# POWER.net
KiCad netlist of a schematic drawn in Altium Designer
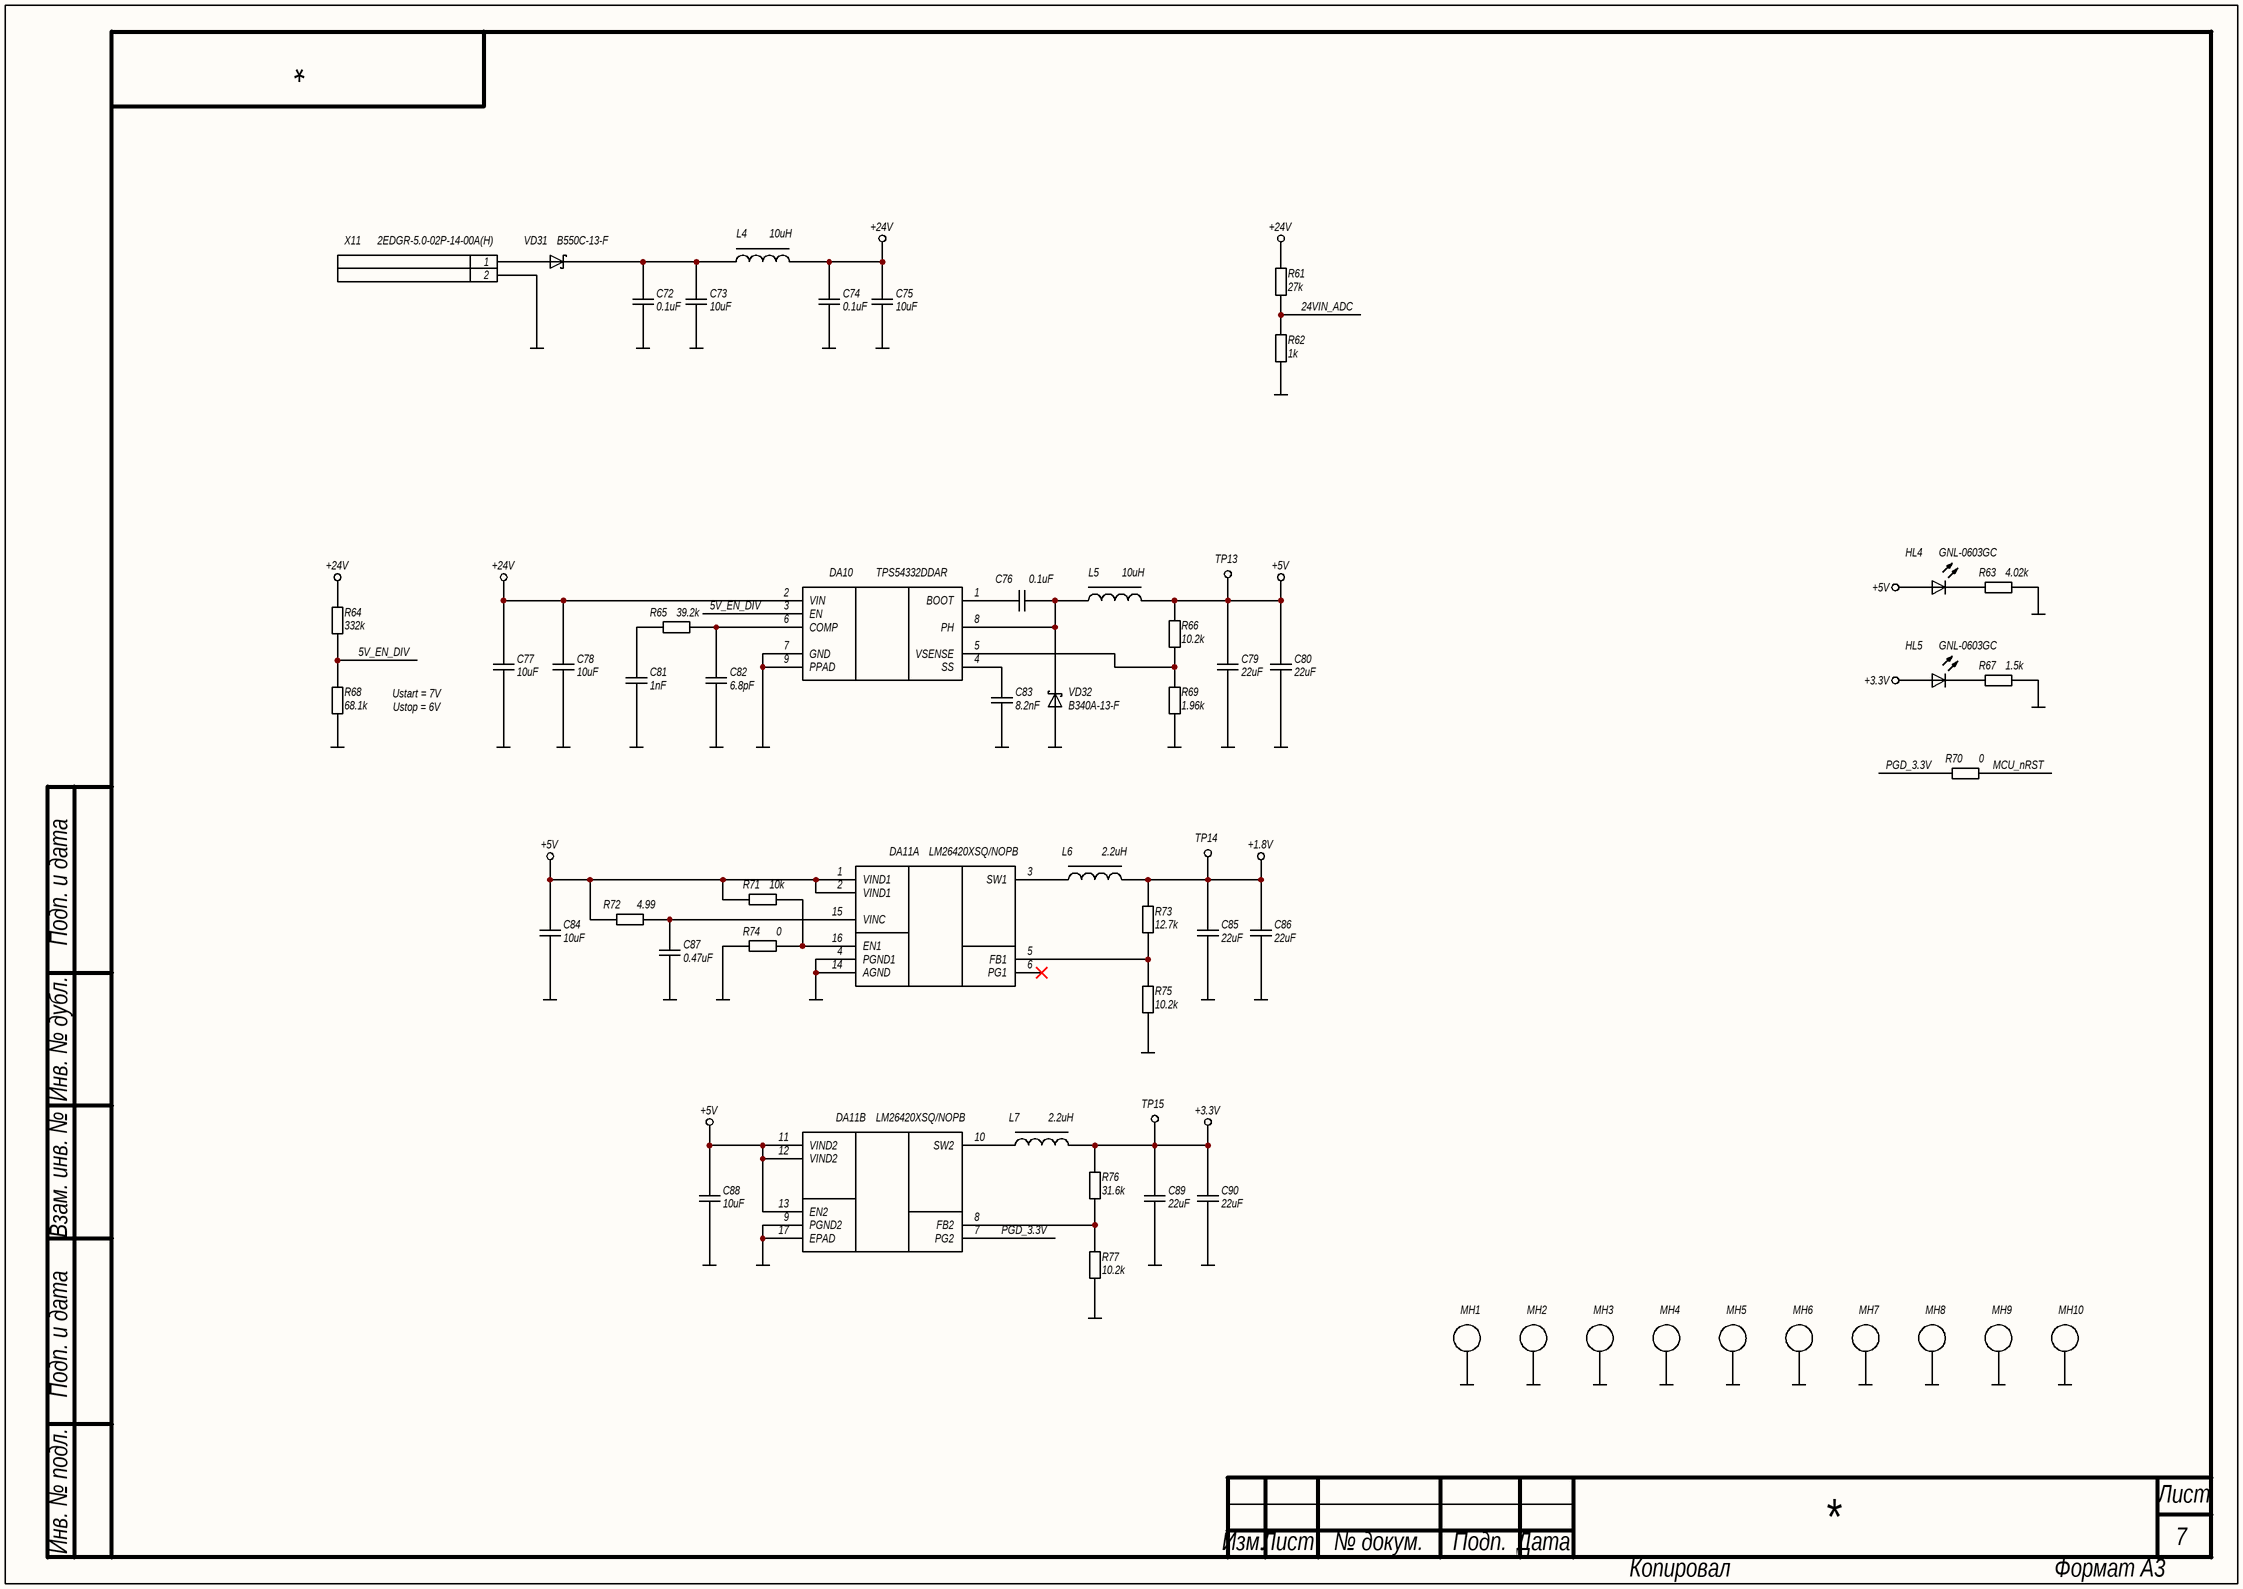
[diagram p0: POWER.SchDoc]

(export (version "E")
  (design (tool "Eeschema 10.0.6"))
  (components
    (comp (ref "C72")
      (value "0.1uF")
      (footprint "C0805N")
      (description "Конденсатор")
      (libsource (lib "Components Library") (part "CAP_FIXED"))
    )
    (comp (ref "C73")
      (value "10uF")
      (footprint "C1206N")
      (description "Конденсатор")
      (libsource (lib "Components Library") (part "CAP_FIXED"))
    )
    (comp (ref "C74")
      (value "0.1uF")
      (footprint "C0805N")
      (description "Конденсатор")
      (libsource (lib "Components Library") (part "CAP_FIXED"))
    )
    (comp (ref "C75")
      (value "10uF")
      (footprint "C1206N")
      (description "Конденсатор")
      (libsource (lib "Components Library") (part "CAP_FIXED"))
    )
    (comp (ref "C76")
      (value "0.1uF")
      (footprint "C0603N")
      (description "Конденсатор")
      (libsource (lib "Components Library") (part "CAP_FIXED"))
    )
    (comp (ref "C77")
      (value "10uF")
      (footprint "C1206N")
      (description "Конденсатор")
      (libsource (lib "Components Library") (part "CAP_FIXED"))
    )
    (comp (ref "C78")
      (value "10uF")
      (footprint "C1206N")
      (description "Конденсатор")
      (libsource (lib "Components Library") (part "CAP_FIXED"))
    )
    (comp (ref "C79")
      (value "22uF")
      (footprint "C0805N")
      (description "Конденсатор")
      (libsource (lib "Components Library") (part "CAP_FIXED"))
    )
    (comp (ref "C80")
      (value "22uF")
      (footprint "C0805N")
      (description "Конденсатор")
      (libsource (lib "Components Library") (part "CAP_FIXED"))
    )
    (comp (ref "C81")
      (value "1nF")
      (footprint "C0603N")
      (description "Конденсатор")
      (libsource (lib "Components Library") (part "CAP_FIXED"))
    )
    (comp (ref "C82")
      (value "6.8pF")
      (footprint "C0603N")
      (description "Конденсатор")
      (libsource (lib "Components Library") (part "CAP_FIXED"))
    )
    (comp (ref "C83")
      (value "8.2nF")
      (footprint "C0603N")
      (description "Конденсатор")
      (libsource (lib "Components Library") (part "CAP_FIXED"))
    )
    (comp (ref "C84")
      (value "10uF")
      (footprint "C0805N")
      (description "Конденсатор")
      (libsource (lib "Components Library") (part "CAP_FIXED"))
    )
    (comp (ref "C85")
      (value "22uF")
      (footprint "C0805N")
      (description "Конденсатор")
      (libsource (lib "Components Library") (part "CAP_FIXED"))
    )
    (comp (ref "C86")
      (value "22uF")
      (footprint "C0805N")
      (description "Конденсатор")
      (libsource (lib "Components Library") (part "CAP_FIXED"))
    )
    (comp (ref "C87")
      (value "0.47uF")
      (footprint "C0603N")
      (description "Конденсатор")
      (libsource (lib "Components Library") (part "CAP_FIXED"))
    )
    (comp (ref "C88")
      (value "10uF")
      (footprint "C0805N")
      (description "Конденсатор")
      (libsource (lib "Components Library") (part "CAP_FIXED"))
    )
    (comp (ref "C89")
      (value "22uF")
      (footprint "C0805N")
      (description "Конденсатор")
      (libsource (lib "Components Library") (part "CAP_FIXED"))
    )
    (comp (ref "C90")
      (value "22uF")
      (footprint "C0805N")
      (description "Конденсатор")
      (libsource (lib "Components Library") (part "CAP_FIXED"))
    )
    (comp (ref "DA10")
      (value "TPS54332DDAR")
      (footprint "SOIC8-EP")
      (description "Микросхема понижающего преобразователя")
      (libsource (lib "Components Library") (part "TPS54332"))
    )
    (comp (ref "DA11")
      (value "LM26420XSQ/NOPB")
      (footprint "RUM0016A")
      (libsource (lib "Components Library") (part "LM26420X"))
    )
    (comp (ref "HL4")
      (value "GNL-0603GC")
      (footprint "LED0603")
      (description "Светодиод")
      (libsource (lib "Components Library") (part "LED"))
    )
    (comp (ref "HL5")
      (value "GNL-0603GC")
      (footprint "LED0603")
      (description "Светодиод")
      (libsource (lib "Components Library") (part "LED"))
    )
    (comp (ref "L4")
      (value "10uH")
      (footprint "SRN8040")
      (description "Дроссель с магнитопроводом")
      (libsource (lib "Components Library") (part "IND_CORE"))
    )
    (comp (ref "L5")
      (value "10uH")
      (footprint "SRN8040")
      (description "Дроссель с магнитопроводом")
      (libsource (lib "Components Library") (part "IND_CORE"))
    )
    (comp (ref "L6")
      (value "2.2uH")
      (footprint "VLS3012HBX")
      (description "Дроссель с магнитопроводом")
      (libsource (lib "Components Library") (part "IND_CORE"))
    )
    (comp (ref "L7")
      (value "2.2uH")
      (footprint "VLS3012HBX")
      (description "Дроссель с магнитопроводом")
      (libsource (lib "Components Library") (part "IND_CORE"))
    )
    (comp (ref "MH1")
      (value "MNT_HOLE_PL")
      (footprint "MH_3.2_5.4_PLATED_VIA")
      (description "Монтажное отверстие, металлизированное")
      (libsource (lib "Components Library") (part "MNT_HOLE_PL"))
    )
    (comp (ref "MH2")
      (value "MNT_HOLE_PL")
      (footprint "MH_3.2_5.4_PLATED_VIA")
      (description "Монтажное отверстие, металлизированное")
      (libsource (lib "Components Library") (part "MNT_HOLE_PL"))
    )
    (comp (ref "MH3")
      (value "MNT_HOLE_PL")
      (footprint "MH_3.2_5.4_PLATED_VIA")
      (description "Монтажное отверстие, металлизированное")
      (libsource (lib "Components Library") (part "MNT_HOLE_PL"))
    )
    (comp (ref "MH4")
      (value "MNT_HOLE_PL")
      (footprint "MH_3.2_5.4_PLATED_VIA")
      (description "Монтажное отверстие, металлизированное")
      (libsource (lib "Components Library") (part "MNT_HOLE_PL"))
    )
    (comp (ref "MH5")
      (value "MNT_HOLE_PL")
      (footprint "MH_3.2_5.4_PLATED_VIA")
      (description "Монтажное отверстие, металлизированное")
      (libsource (lib "Components Library") (part "MNT_HOLE_PL"))
    )
    (comp (ref "MH6")
      (value "MNT_HOLE_PL")
      (footprint "MH_3.2_5.4_PLATED_VIA")
      (description "Монтажное отверстие, металлизированное")
      (libsource (lib "Components Library") (part "MNT_HOLE_PL"))
    )
    (comp (ref "MH7")
      (value "MNT_HOLE_PL")
      (footprint "MH_3.2_5.4_PLATED_VIA")
      (description "Монтажное отверстие, металлизированное")
      (libsource (lib "Components Library") (part "MNT_HOLE_PL"))
    )
    (comp (ref "MH8")
      (value "MNT_HOLE_PL")
      (footprint "MH_3.2_5.4_PLATED_VIA")
      (description "Монтажное отверстие, металлизированное")
      (libsource (lib "Components Library") (part "MNT_HOLE_PL"))
    )
    (comp (ref "MH9")
      (value "MNT_HOLE_PL")
      (footprint "MH_3.2_5.4_PLATED_VIA")
      (description "Монтажное отверстие, металлизированное")
      (libsource (lib "Components Library") (part "MNT_HOLE_PL"))
    )
    (comp (ref "MH10")
      (value "MNT_HOLE_PL")
      (footprint "MH_3.2_5.4_PLATED_VIA")
      (description "Монтажное отверстие, металлизированное")
      (libsource (lib "Components Library") (part "MNT_HOLE_PL"))
    )
    (comp (ref "R61")
      (value "27k")
      (footprint "R0603N")
      (description "Резистор")
      (libsource (lib "") (part "RES_FIXED_1"))
    )
    (comp (ref "R62")
      (value "1k")
      (footprint "R0603N")
      (description "Резистор")
      (libsource (lib "") (part "RES_FIXED_1"))
    )
    (comp (ref "R63")
      (value "4.02k")
      (footprint "R0603N")
      (description "Резистор")
      (libsource (lib "") (part "RES_FIXED_2"))
    )
    (comp (ref "R64")
      (value "332k")
      (footprint "R0603N")
      (description "Резистор")
      (libsource (lib "Components Library") (part "RES_FIXED"))
    )
    (comp (ref "R65")
      (value "39.2k")
      (footprint "R0603N")
      (description "Резистор")
      (libsource (lib "") (part "RES_FIXED_2"))
    )
    (comp (ref "R66")
      (value "10.2k")
      (footprint "R0603N")
      (description "Резистор")
      (libsource (lib "Components Library") (part "RES_FIXED"))
    )
    (comp (ref "R67")
      (value "1.5k")
      (footprint "R0603N")
      (description "Резистор")
      (libsource (lib "") (part "RES_FIXED_2"))
    )
    (comp (ref "R68")
      (value "68.1k")
      (footprint "R0603N")
      (description "Резистор")
      (libsource (lib "Components Library") (part "RES_FIXED"))
    )
    (comp (ref "R69")
      (value "1.96k")
      (footprint "R0603N")
      (description "Резистор")
      (libsource (lib "Components Library") (part "RES_FIXED"))
    )
    (comp (ref "R70")
      (value "0")
      (footprint "R0603N")
      (description "Резистор")
      (libsource (lib "") (part "RES_FIXED_3"))
    )
    (comp (ref "R71")
      (value "10k")
      (footprint "R0603N")
      (description "Резистор")
      (libsource (lib "") (part "RES_FIXED_2"))
    )
    (comp (ref "R72")
      (value "4.99")
      (footprint "R0603N")
      (description "Резистор")
      (libsource (lib "") (part "RES_FIXED_2"))
    )
    (comp (ref "R73")
      (value "12.7k")
      (footprint "R0603N")
      (description "Резистор")
      (libsource (lib "Components Library") (part "RES_FIXED"))
    )
    (comp (ref "R74")
      (value "0")
      (footprint "R0603N")
      (description "Резистор")
      (libsource (lib "") (part "RES_FIXED_2"))
    )
    (comp (ref "R75")
      (value "10.2k")
      (footprint "R0603N")
      (description "Резистор")
      (libsource (lib "Components Library") (part "RES_FIXED"))
    )
    (comp (ref "R76")
      (value "31.6k")
      (footprint "R0603N")
      (description "Резистор")
      (libsource (lib "Components Library") (part "RES_FIXED"))
    )
    (comp (ref "R77")
      (value "10.2k")
      (footprint "R0603N")
      (description "Резистор")
      (libsource (lib "Components Library") (part "RES_FIXED"))
    )
    (comp (ref "TP13")
      (value "TEST_POINT")
      (footprint "TP_RPAD_0.8MM")
      (description "Контрольная точка")
      (libsource (lib "Components Library") (part "TEST_POINT"))
    )
    (comp (ref "TP14")
      (value "TEST_POINT")
      (footprint "TP_RPAD_0.8MM")
      (description "Контрольная точка")
      (libsource (lib "Components Library") (part "TEST_POINT"))
    )
    (comp (ref "TP15")
      (value "TEST_POINT")
      (footprint "TP_RPAD_0.8MM")
      (description "Контрольная точка")
      (libsource (lib "Components Library") (part "TEST_POINT"))
    )
    (comp (ref "VD31")
      (value "B550C-13-F")
      (footprint "SMC")
      (description "Диод Шоттки")
      (libsource (lib "Components Library") (part "SCHOTTKY"))
    )
    (comp (ref "VD32")
      (value "B340A-13-F")
      (footprint "SMA")
      (description "Диод Шоттки")
      (libsource (lib "Components Library") (part "SCHOTTKY"))
    )
    (comp (ref "X11")
      (value "2EDGR-5.0-02P-14-00A(H)")
      (footprint "2EDGR-5.0-02P-14-00A(H)")
      (description "Разъем, 2 контакта")
      (libsource (lib "Components Library") (part "Connector 2"))
    )
  )
  (nets
    (net (code "1") (name "+1.8V") (class "Default")
      (node (ref "C85") (pin "2") (pinfunction "2_2") (pintype "passive"))
      (node (ref "C86") (pin "2") (pinfunction "2_2") (pintype "passive"))
      (node (ref "L6") (pin "2") (pinfunction "2_2") (pintype "passive"))
      (node (ref "R73") (pin "1") (pinfunction "1_1") (pintype "passive"))
      (node (ref "TP14") (pin "1") (pinfunction "1_1") (pintype "passive"))
    )
    (net (code "2") (name "+3.3V") (class "Default")
      (node (ref "C89") (pin "2") (pinfunction "2_2") (pintype "passive"))
      (node (ref "C90") (pin "2") (pinfunction "2_2") (pintype "passive"))
      (node (ref "HL5") (pin "2") (pinfunction "A_2") (pintype "passive"))
      (node (ref "L7") (pin "2") (pinfunction "2_2") (pintype "passive"))
      (node (ref "R76") (pin "1") (pinfunction "1_1") (pintype "passive"))
      (node (ref "TP15") (pin "1") (pinfunction "1_1") (pintype "passive"))
    )
    (net (code "3") (name "+5V") (class "Default")
      (node (ref "C79") (pin "2") (pinfunction "2_2") (pintype "passive"))
      (node (ref "C80") (pin "2") (pinfunction "2_2") (pintype "passive"))
      (node (ref "C84") (pin "2") (pinfunction "2_2") (pintype "passive"))
      (node (ref "C88") (pin "2") (pinfunction "2_2") (pintype "passive"))
      (node (ref "DA11") (pin "1") (pinfunction "VIND1_1") (pintype "power_in"))
      (node (ref "DA11") (pin "11") (pinfunction "VIND2_11") (pintype "power_in"))
      (node (ref "DA11") (pin "12") (pinfunction "VIND2_12") (pintype "power_in"))
      (node (ref "DA11") (pin "13") (pinfunction "EN2_13") (pintype "power_in"))
      (node (ref "DA11") (pin "2") (pinfunction "VIND1_2") (pintype "power_in"))
      (node (ref "HL4") (pin "2") (pinfunction "A_2") (pintype "passive"))
      (node (ref "L5") (pin "2") (pinfunction "2_2") (pintype "passive"))
      (node (ref "R66") (pin "1") (pinfunction "1_1") (pintype "passive"))
      (node (ref "R71") (pin "2") (pinfunction "2_2") (pintype "passive"))
      (node (ref "R72") (pin "2") (pinfunction "2_2") (pintype "passive"))
      (node (ref "TP13") (pin "1") (pinfunction "1_1") (pintype "passive"))
    )
    (net (code "4") (name "+24V") (class "Default")
      (node (ref "C74") (pin "2") (pinfunction "2_2") (pintype "passive"))
      (node (ref "C75") (pin "2") (pinfunction "2_2") (pintype "passive"))
      (node (ref "C77") (pin "2") (pinfunction "2_2") (pintype "passive"))
      (node (ref "C78") (pin "2") (pinfunction "2_2") (pintype "passive"))
      (node (ref "DA10") (pin "2") (pinfunction "VIN_2") (pintype "power_in"))
      (node (ref "L4") (pin "2") (pinfunction "2_2") (pintype "passive"))
      (node (ref "R61") (pin "2") (pinfunction "2_2") (pintype "passive"))
      (node (ref "R64") (pin "1") (pinfunction "1_1") (pintype "passive"))
    )
    (net (code "5") (name "/5V_EN_DIV") (class "Default")
      (node (ref "DA10") (pin "3") (pinfunction "EN_3") (pintype "power_in"))
      (node (ref "R64") (pin "2") (pinfunction "2_2") (pintype "passive"))
      (node (ref "R68") (pin "1") (pinfunction "1_1") (pintype "passive"))
    )
    (net (code "6") (name "/24VIN_ADC") (class "Default")
      (node (ref "R61") (pin "1") (pinfunction "1_1") (pintype "passive"))
      (node (ref "R62") (pin "2") (pinfunction "2_2") (pintype "passive"))
    )
    (net (code "7") (name "/MCU_nRST") (class "Default")
      (node (ref "R70") (pin "2") (pinfunction "2_2") (pintype "passive"))
    )
    (net (code "8") (name "/PGD_3.3V") (class "Default")
      (node (ref "DA11") (pin "7") (pinfunction "PG2_7") (pintype "power_in"))
      (node (ref "R70") (pin "1") (pinfunction "1_1") (pintype "passive"))
    )
    (net (code "9") (name "GND") (class "Default")
      (node (ref "C72") (pin "1") (pinfunction "1_1") (pintype "passive"))
      (node (ref "C73") (pin "1") (pinfunction "1_1") (pintype "passive"))
      (node (ref "C74") (pin "1") (pinfunction "1_1") (pintype "passive"))
      (node (ref "C75") (pin "1") (pinfunction "1_1") (pintype "passive"))
      (node (ref "C77") (pin "1") (pinfunction "1_1") (pintype "passive"))
      (node (ref "C78") (pin "1") (pinfunction "1_1") (pintype "passive"))
      (node (ref "C79") (pin "1") (pinfunction "1_1") (pintype "passive"))
      (node (ref "C80") (pin "1") (pinfunction "1_1") (pintype "passive"))
      (node (ref "C81") (pin "1") (pinfunction "1_1") (pintype "passive"))
      (node (ref "C82") (pin "1") (pinfunction "1_1") (pintype "passive"))
      (node (ref "C83") (pin "1") (pinfunction "1_1") (pintype "passive"))
      (node (ref "C84") (pin "1") (pinfunction "1_1") (pintype "passive"))
      (node (ref "C85") (pin "1") (pinfunction "1_1") (pintype "passive"))
      (node (ref "C86") (pin "1") (pinfunction "1_1") (pintype "passive"))
      (node (ref "C87") (pin "1") (pinfunction "1_1") (pintype "passive"))
      (node (ref "C88") (pin "1") (pinfunction "1_1") (pintype "passive"))
      (node (ref "C89") (pin "1") (pinfunction "1_1") (pintype "passive"))
      (node (ref "C90") (pin "1") (pinfunction "1_1") (pintype "passive"))
      (node (ref "DA10") (pin "7") (pinfunction "GND_7") (pintype "power_in"))
      (node (ref "DA10") (pin "9") (pinfunction "PPAD_9") (pintype "power_in"))
      (node (ref "DA11") (pin "14") (pinfunction "AGND_14") (pintype "power_in"))
      (node (ref "DA11") (pin "17") (pinfunction "EPAD_17") (pintype "power_in"))
      (node (ref "DA11") (pin "4") (pinfunction "PGND1_4") (pintype "power_in"))
      (node (ref "DA11") (pin "9") (pinfunction "PGND2_9") (pintype "power_in"))
      (node (ref "MH1") (pin "1") (pinfunction "1_1") (pintype "passive"))
      (node (ref "MH10") (pin "1") (pinfunction "1_1") (pintype "passive"))
      (node (ref "MH2") (pin "1") (pinfunction "1_1") (pintype "passive"))
      (node (ref "MH3") (pin "1") (pinfunction "1_1") (pintype "passive"))
      (node (ref "MH4") (pin "1") (pinfunction "1_1") (pintype "passive"))
      (node (ref "MH5") (pin "1") (pinfunction "1_1") (pintype "passive"))
      (node (ref "MH6") (pin "1") (pinfunction "1_1") (pintype "passive"))
      (node (ref "MH7") (pin "1") (pinfunction "1_1") (pintype "passive"))
      (node (ref "MH8") (pin "1") (pinfunction "1_1") (pintype "passive"))
      (node (ref "MH9") (pin "1") (pinfunction "1_1") (pintype "passive"))
      (node (ref "R62") (pin "1") (pinfunction "1_1") (pintype "passive"))
      (node (ref "R63") (pin "1") (pinfunction "1_1") (pintype "passive"))
      (node (ref "R67") (pin "1") (pinfunction "1_1") (pintype "passive"))
      (node (ref "R68") (pin "2") (pinfunction "2_2") (pintype "passive"))
      (node (ref "R69") (pin "2") (pinfunction "2_2") (pintype "passive"))
      (node (ref "R74") (pin "2") (pinfunction "2_2") (pintype "passive"))
      (node (ref "R75") (pin "2") (pinfunction "2_2") (pintype "passive"))
      (node (ref "R77") (pin "2") (pinfunction "2_2") (pintype "passive"))
      (node (ref "VD32") (pin "2") (pinfunction "A_2") (pintype "passive"))
      (node (ref "X11") (pin "2") (pinfunction "2_2") (pintype "power_in"))
    )
    (net (code "10") (name "Net-(C81-Pad2)") (class "Default")
      (node (ref "C81") (pin "2") (pinfunction "2_2") (pintype "passive"))
      (node (ref "R65") (pin "2") (pinfunction "2_2") (pintype "passive"))
    )
    (net (code "11") (name "Net-(DA10-BOOT)") (class "Default")
      (node (ref "C76") (pin "2") (pinfunction "2_2") (pintype "passive"))
      (node (ref "DA10") (pin "1") (pinfunction "BOOT_1") (pintype "power_in"))
    )
    (net (code "12") (name "Net-(DA10-COMP)") (class "Default")
      (node (ref "C82") (pin "2") (pinfunction "2_2") (pintype "passive"))
      (node (ref "DA10") (pin "6") (pinfunction "COMP_6") (pintype "power_in"))
      (node (ref "R65") (pin "1") (pinfunction "1_1") (pintype "passive"))
    )
    (net (code "13") (name "Net-(DA10-PH)") (class "Default")
      (node (ref "C76") (pin "1") (pinfunction "1_1") (pintype "passive"))
      (node (ref "DA10") (pin "8") (pinfunction "PH_8") (pintype "power_in"))
      (node (ref "L5") (pin "1") (pinfunction "1_1") (pintype "passive"))
      (node (ref "VD32") (pin "1") (pinfunction "K_1") (pintype "passive"))
    )
    (net (code "14") (name "Net-(DA10-SS)") (class "Default")
      (node (ref "C83") (pin "2") (pinfunction "2_2") (pintype "passive"))
      (node (ref "DA10") (pin "4") (pinfunction "SS_4") (pintype "power_in"))
    )
    (net (code "15") (name "Net-(DA10-VSENSE)") (class "Default")
      (node (ref "DA10") (pin "5") (pinfunction "VSENSE_5") (pintype "power_in"))
      (node (ref "R66") (pin "2") (pinfunction "2_2") (pintype "passive"))
      (node (ref "R69") (pin "1") (pinfunction "1_1") (pintype "passive"))
    )
    (net (code "16") (name "Net-(DA11A-EN1)") (class "Default")
      (node (ref "DA11") (pin "16") (pinfunction "EN1_16") (pintype "power_in"))
      (node (ref "R71") (pin "1") (pinfunction "1_1") (pintype "passive"))
      (node (ref "R74") (pin "1") (pinfunction "1_1") (pintype "passive"))
    )
    (net (code "17") (name "Net-(DA11A-FB1)") (class "Default")
      (node (ref "DA11") (pin "5") (pinfunction "FB1_5") (pintype "power_in"))
      (node (ref "R73") (pin "2") (pinfunction "2_2") (pintype "passive"))
      (node (ref "R75") (pin "1") (pinfunction "1_1") (pintype "passive"))
    )
    (net (code "18") (name "Net-(DA11A-SW1)") (class "Default")
      (node (ref "DA11") (pin "3") (pinfunction "SW1_3") (pintype "power_in"))
      (node (ref "L6") (pin "1") (pinfunction "1_1") (pintype "passive"))
    )
    (net (code "19") (name "Net-(DA11A-VINC)") (class "Default")
      (node (ref "C87") (pin "2") (pinfunction "2_2") (pintype "passive"))
      (node (ref "DA11") (pin "15") (pinfunction "VINC_15") (pintype "power_in"))
      (node (ref "R72") (pin "1") (pinfunction "1_1") (pintype "passive"))
    )
    (net (code "20") (name "Net-(DA11B-FB2)") (class "Default")
      (node (ref "DA11") (pin "8") (pinfunction "FB2_8") (pintype "power_in"))
      (node (ref "R76") (pin "2") (pinfunction "2_2") (pintype "passive"))
      (node (ref "R77") (pin "1") (pinfunction "1_1") (pintype "passive"))
    )
    (net (code "21") (name "Net-(DA11B-SW2)") (class "Default")
      (node (ref "DA11") (pin "10") (pinfunction "SW2_10") (pintype "power_in"))
      (node (ref "L7") (pin "1") (pinfunction "1_1") (pintype "passive"))
    )
    (net (code "22") (name "Net-(HL4-K)") (class "Default")
      (node (ref "HL4") (pin "1") (pinfunction "K_1") (pintype "passive"))
      (node (ref "R63") (pin "2") (pinfunction "2_2") (pintype "passive"))
    )
    (net (code "23") (name "Net-(HL5-K)") (class "Default")
      (node (ref "HL5") (pin "1") (pinfunction "K_1") (pintype "passive"))
      (node (ref "R67") (pin "2") (pinfunction "2_2") (pintype "passive"))
    )
    (net (code "24") (name "Net-(VD31-A)") (class "Default")
      (node (ref "VD31") (pin "2") (pinfunction "A_2") (pintype "passive"))
      (node (ref "X11") (pin "1") (pinfunction "1_1") (pintype "power_in"))
    )
    (net (code "25") (name "Net-(VD31-K)") (class "Default")
      (node (ref "C72") (pin "2") (pinfunction "2_2") (pintype "passive"))
      (node (ref "C73") (pin "2") (pinfunction "2_2") (pintype "passive"))
      (node (ref "L4") (pin "1") (pinfunction "1_1") (pintype "passive"))
      (node (ref "VD31") (pin "1") (pinfunction "K_1") (pintype "passive"))
    )
    (net (code "26") (name "unconnected-(DA11A-PG1-Pad6)") (class "Default")
      (node (ref "DA11") (pin "6") (pinfunction "PG1_6") (pintype "power_in+no_connect"))
    )
  )
)
